# interruptorcontrolado.net
KiCad netlist of a schematic drawn in EAGLE
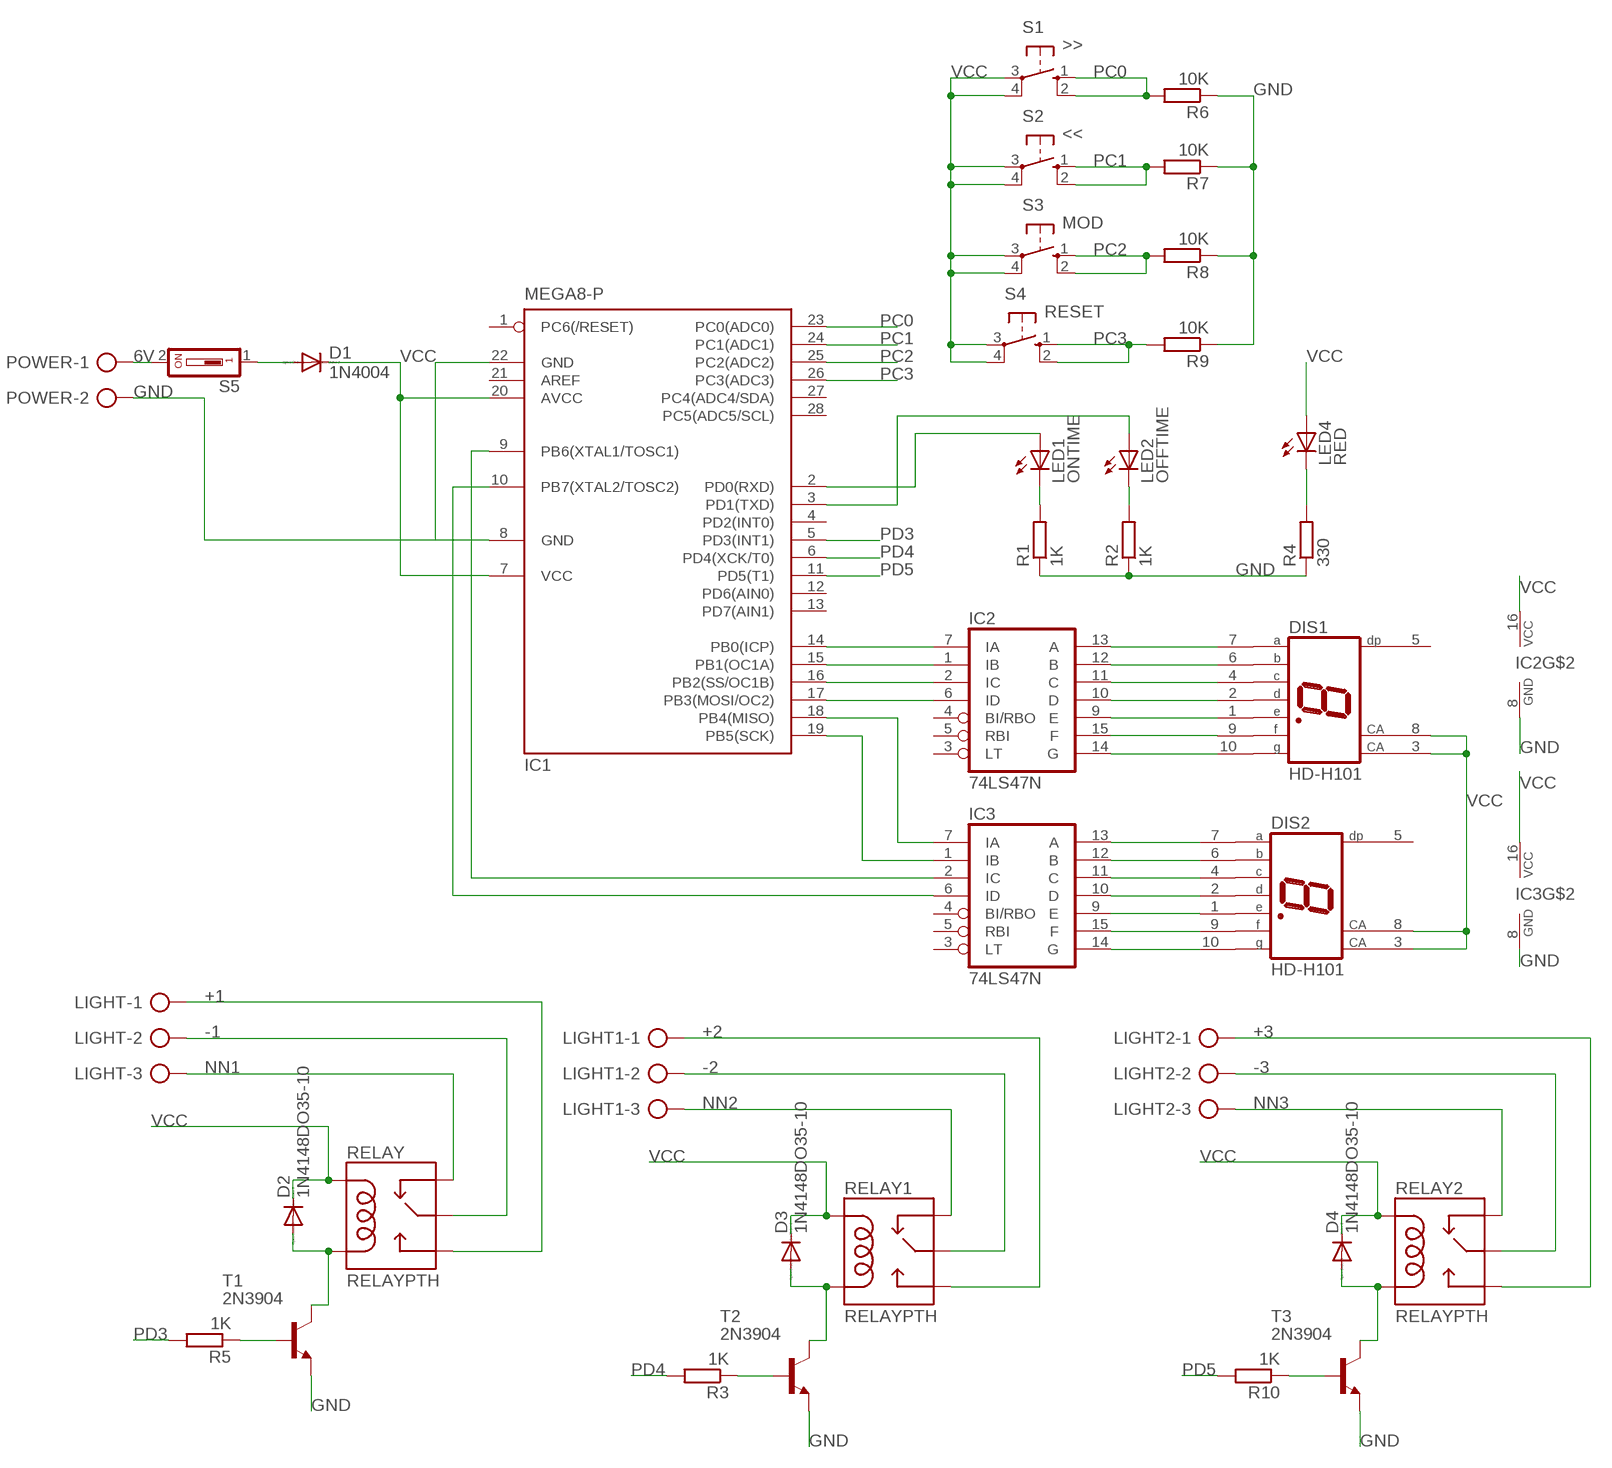
[diagram p0: schematic, sheet 1]

(export (version "E")
  (design (tool "Eeschema 10.0.6"))
  (components
    (comp (ref "D1")
      (value "1N4004")
      (footprint "eagle-import:DO41-10")
      (libsource (lib "eagle-import") (part "1N4004"))
    )
    (comp (ref "D2")
      (value "1N4148DO35-10")
      (footprint "eagle-import:DO35-10")
      (libsource (lib "eagle-import") (part "1N4148DO35-10"))
    )
    (comp (ref "D3")
      (value "1N4148DO35-10")
      (footprint "eagle-import:DO35-10")
      (libsource (lib "eagle-import") (part "1N4148DO35-10"))
    )
    (comp (ref "D4")
      (value "1N4148DO35-10")
      (footprint "eagle-import:DO35-10")
      (libsource (lib "eagle-import") (part "1N4148DO35-10"))
    )
    (comp (ref "DIS1")
      (value "HD-H101")
      (footprint "eagle-import:HDSP-M")
      (libsource (lib "eagle-import") (part "HD-H101"))
    )
    (comp (ref "DIS2")
      (value "HD-H101")
      (footprint "eagle-import:HDSP-M")
      (libsource (lib "eagle-import") (part "HD-H101"))
    )
    (comp (ref "IC1")
      (value "MEGA8-P")
      (footprint "eagle-import:DIL28-3")
      (libsource (lib "eagle-import") (part "MEGA8-P"))
    )
    (comp (ref "IC2")
      (value "74LS47N")
      (footprint "eagle-import:DIL16")
      (libsource (lib "eagle-import") (part "7447NLS"))
    )
    (comp (ref "IC3")
      (value "74LS47N")
      (footprint "eagle-import:DIL16")
      (libsource (lib "eagle-import") (part "7447NLS"))
    )
    (comp (ref "LED1")
      (value "ONTIME")
      (footprint "eagle-import:LED5MM")
      (libsource (lib "eagle-import") (part "LED5MM"))
    )
    (comp (ref "LED2")
      (value "OFFTIME")
      (footprint "eagle-import:LED5MM")
      (libsource (lib "eagle-import") (part "LED5MM"))
    )
    (comp (ref "LED4")
      (value "RED")
      (footprint "eagle-import:LED5MM")
      (libsource (lib "eagle-import") (part "LED5MM"))
    )
    (comp (ref "LIGHT")
      (value "AK500/3")
      (footprint "eagle-import:AK500_3")
      (libsource (lib "eagle-import") (part "AK500/3"))
    )
    (comp (ref "LIGHT1")
      (value "AK500/3")
      (footprint "eagle-import:AK500_3")
      (libsource (lib "eagle-import") (part "AK500/3"))
    )
    (comp (ref "LIGHT2")
      (value "AK500/3")
      (footprint "eagle-import:AK500_3")
      (libsource (lib "eagle-import") (part "AK500/3"))
    )
    (comp (ref "POWER")
      (value "AK500/2")
      (footprint "eagle-import:AK500_2")
      (libsource (lib "eagle-import") (part "AK500/2"))
    )
    (comp (ref "R1")
      (value "1K")
      (footprint "eagle-import:0207_10")
      (libsource (lib "eagle-import") (part "R-EU_0207/10"))
    )
    (comp (ref "R2")
      (value "1K")
      (footprint "eagle-import:0207_10")
      (libsource (lib "eagle-import") (part "R-EU_0207/10"))
    )
    (comp (ref "R3")
      (value "1K")
      (footprint "eagle-import:0207_10")
      (libsource (lib "eagle-import") (part "R-EU_0207/10"))
    )
    (comp (ref "R4")
      (value "330")
      (footprint "eagle-import:0207_10")
      (libsource (lib "eagle-import") (part "R-EU_0207/10"))
    )
    (comp (ref "R5")
      (value "1K")
      (footprint "eagle-import:0207_10")
      (libsource (lib "eagle-import") (part "R-EU_0207/10"))
    )
    (comp (ref "R6")
      (value "10K")
      (footprint "eagle-import:0207_10")
      (libsource (lib "eagle-import") (part "R-EU_0207/10"))
    )
    (comp (ref "R7")
      (value "10K")
      (footprint "eagle-import:0207_10")
      (libsource (lib "eagle-import") (part "R-EU_0207/10"))
    )
    (comp (ref "R8")
      (value "10K")
      (footprint "eagle-import:0207_10")
      (libsource (lib "eagle-import") (part "R-EU_0207/10"))
    )
    (comp (ref "R9")
      (value "10K")
      (footprint "eagle-import:0207_10")
      (libsource (lib "eagle-import") (part "R-EU_0207/10"))
    )
    (comp (ref "R10")
      (value "1K")
      (footprint "eagle-import:0207_10")
      (libsource (lib "eagle-import") (part "R-EU_0207/10"))
    )
    (comp (ref "RELAY")
      (value "RELAYPTH")
      (footprint "eagle-import:SRD-05VDC-SL-C")
      (libsource (lib "eagle-import") (part "RELAYPTH"))
    )
    (comp (ref "RELAY1")
      (value "RELAYPTH")
      (footprint "eagle-import:SRD-05VDC-SL-C")
      (libsource (lib "eagle-import") (part "RELAYPTH"))
    )
    (comp (ref "RELAY2")
      (value "RELAYPTH")
      (footprint "eagle-import:SRD-05VDC-SL-C")
      (libsource (lib "eagle-import") (part "RELAYPTH"))
    )
    (comp (ref "S1")
      (value ">>")
      (footprint "eagle-import:B3F-10XX")
      (fields (field (name "MPN") "B3F-1000"))
      (libsource (lib "eagle-import") (part "10-XX"))
    )
    (comp (ref "S2")
      (value "<<")
      (footprint "eagle-import:B3F-10XX")
      (fields (field (name "MPN") "B3F-1000"))
      (libsource (lib "eagle-import") (part "10-XX"))
    )
    (comp (ref "S3")
      (value "MOD")
      (footprint "eagle-import:B3F-10XX")
      (fields (field (name "MPN") "B3F-1000"))
      (libsource (lib "eagle-import") (part "10-XX"))
    )
    (comp (ref "S4")
      (value "RESET")
      (footprint "eagle-import:B3F-10XX")
      (fields (field (name "MPN") "B3F-1000"))
      (libsource (lib "eagle-import") (part "10-XX"))
    )
    (comp (ref "S5")
      (value "SD4-01")
      (footprint "eagle-import:SD4-01")
      (libsource (lib "eagle-import") (part "SD4-01"))
    )
    (comp (ref "T1")
      (value "2N3904")
      (footprint "eagle-import:TO92")
      (libsource (lib "eagle-import") (part "2N3904"))
    )
    (comp (ref "T2")
      (value "2N3904")
      (footprint "eagle-import:TO92")
      (libsource (lib "eagle-import") (part "2N3904"))
    )
    (comp (ref "T3")
      (value "2N3904")
      (footprint "eagle-import:TO92")
      (libsource (lib "eagle-import") (part "2N3904"))
    )
  )
  (nets
    (net (code "1") (name "/+1") (class "Default")
      (node (ref "LIGHT") (pin "1") (pinfunction "KL_1") (pintype "passive"))
      (node (ref "RELAY") (pin "SWOPEN") (pinfunction "SWOPEN_SWOPEN") (pintype "bidirectional"))
    )
    (net (code "2") (name "/+2") (class "Default")
      (node (ref "LIGHT1") (pin "1") (pinfunction "KL_1") (pintype "passive"))
      (node (ref "RELAY1") (pin "SWOPEN") (pinfunction "SWOPEN_SWOPEN") (pintype "bidirectional"))
    )
    (net (code "3") (name "/+3") (class "Default")
      (node (ref "LIGHT2") (pin "1") (pinfunction "KL_1") (pintype "passive"))
      (node (ref "RELAY2") (pin "SWOPEN") (pinfunction "SWOPEN_SWOPEN") (pintype "bidirectional"))
    )
    (net (code "4") (name "/-1") (class "Default")
      (node (ref "LIGHT") (pin "2") (pinfunction "KL_2") (pintype "passive"))
      (node (ref "RELAY") (pin "SWCOMMON") (pinfunction "SWCOMMON_SWCOMMON") (pintype "bidirectional"))
    )
    (net (code "5") (name "/-2") (class "Default")
      (node (ref "LIGHT1") (pin "2") (pinfunction "KL_2") (pintype "passive"))
      (node (ref "RELAY1") (pin "SWCOMMON") (pinfunction "SWCOMMON_SWCOMMON") (pintype "bidirectional"))
    )
    (net (code "6") (name "/-3") (class "Default")
      (node (ref "LIGHT2") (pin "2") (pinfunction "KL_2") (pintype "passive"))
      (node (ref "RELAY2") (pin "SWCOMMON") (pinfunction "SWCOMMON_SWCOMMON") (pintype "bidirectional"))
    )
    (net (code "7") (name "/6V") (class "Default")
      (node (ref "POWER") (pin "1") (pinfunction "KL_1") (pintype "passive"))
      (node (ref "S5") (pin "2") (pinfunction "2_2") (pintype "passive"))
    )
    (net (code "8") (name "/GND") (class "Default")
      (node (ref "IC1") (pin "22") (pinfunction "GND_22") (pintype "power_in"))
      (node (ref "IC1") (pin "8") (pinfunction "GND_8") (pintype "power_in"))
      (node (ref "IC2") (pin "8") (pinfunction "GND_8") (pintype "power_in"))
      (node (ref "IC3") (pin "8") (pinfunction "GND_8") (pintype "power_in"))
      (node (ref "POWER") (pin "2") (pinfunction "KL_2") (pintype "passive"))
      (node (ref "R1") (pin "1") (pinfunction "1_1") (pintype "passive"))
      (node (ref "R2") (pin "1") (pinfunction "1_1") (pintype "passive"))
      (node (ref "R4") (pin "1") (pinfunction "1_1") (pintype "passive"))
      (node (ref "R6") (pin "1") (pinfunction "1_1") (pintype "passive"))
      (node (ref "R7") (pin "1") (pinfunction "1_1") (pintype "passive"))
      (node (ref "R8") (pin "1") (pinfunction "1_1") (pintype "passive"))
      (node (ref "R9") (pin "1") (pinfunction "1_1") (pintype "passive"))
      (node (ref "T1") (pin "3") (pinfunction "E_3") (pintype "passive"))
      (node (ref "T2") (pin "3") (pinfunction "E_3") (pintype "passive"))
      (node (ref "T3") (pin "3") (pinfunction "E_3") (pintype "passive"))
    )
    (net (code "9") (name "/NN1") (class "Default")
      (node (ref "LIGHT") (pin "3") (pinfunction "KL_3") (pintype "passive"))
      (node (ref "RELAY") (pin "SWCLOSED") (pinfunction "SWCLOSE_SWCLOSED") (pintype "bidirectional"))
    )
    (net (code "10") (name "/NN2") (class "Default")
      (node (ref "LIGHT1") (pin "3") (pinfunction "KL_3") (pintype "passive"))
      (node (ref "RELAY1") (pin "SWCLOSED") (pinfunction "SWCLOSE_SWCLOSED") (pintype "bidirectional"))
    )
    (net (code "11") (name "/NN3") (class "Default")
      (node (ref "LIGHT2") (pin "3") (pinfunction "KL_3") (pintype "passive"))
      (node (ref "RELAY2") (pin "SWCLOSED") (pinfunction "SWCLOSE_SWCLOSED") (pintype "bidirectional"))
    )
    (net (code "12") (name "/PC0") (class "Default")
      (node (ref "IC1") (pin "23") (pinfunction "PC0(ADC0)_23") (pintype "bidirectional"))
      (node (ref "R6") (pin "2") (pinfunction "2_2") (pintype "passive"))
      (node (ref "S1") (pin "1") (pinfunction "S_1") (pintype "passive"))
      (node (ref "S1") (pin "2") (pinfunction "S1_2") (pintype "passive"))
    )
    (net (code "13") (name "/PC1") (class "Default")
      (node (ref "IC1") (pin "24") (pinfunction "PC1(ADC1)_24") (pintype "bidirectional"))
      (node (ref "R7") (pin "2") (pinfunction "2_2") (pintype "passive"))
      (node (ref "S2") (pin "1") (pinfunction "S_1") (pintype "passive"))
      (node (ref "S2") (pin "2") (pinfunction "S1_2") (pintype "passive"))
    )
    (net (code "14") (name "/PC2") (class "Default")
      (node (ref "IC1") (pin "25") (pinfunction "PC2(ADC2)_25") (pintype "bidirectional"))
      (node (ref "R8") (pin "2") (pinfunction "2_2") (pintype "passive"))
      (node (ref "S3") (pin "1") (pinfunction "S_1") (pintype "passive"))
      (node (ref "S3") (pin "2") (pinfunction "S1_2") (pintype "passive"))
    )
    (net (code "15") (name "/PC3") (class "Default")
      (node (ref "IC1") (pin "26") (pinfunction "PC3(ADC3)_26") (pintype "bidirectional"))
      (node (ref "R9") (pin "2") (pinfunction "2_2") (pintype "passive"))
      (node (ref "S4") (pin "1") (pinfunction "S_1") (pintype "passive"))
      (node (ref "S4") (pin "2") (pinfunction "S1_2") (pintype "passive"))
    )
    (net (code "16") (name "/PD3") (class "Default")
      (node (ref "IC1") (pin "5") (pinfunction "PD3(INT1)_5") (pintype "bidirectional"))
      (node (ref "R5") (pin "2") (pinfunction "2_2") (pintype "passive"))
    )
    (net (code "17") (name "/PD4") (class "Default")
      (node (ref "IC1") (pin "6") (pinfunction "PD4(XCK/T0)_6") (pintype "bidirectional"))
      (node (ref "R3") (pin "2") (pinfunction "2_2") (pintype "passive"))
    )
    (net (code "18") (name "/PD5") (class "Default")
      (node (ref "IC1") (pin "11") (pinfunction "PD5(T1)_11") (pintype "bidirectional"))
      (node (ref "R10") (pin "2") (pinfunction "2_2") (pintype "passive"))
    )
    (net (code "19") (name "/VCC") (class "Default")
      (node (ref "D1") (pin "C") (pinfunction "C_C") (pintype "passive"))
      (node (ref "D2") (pin "C") (pinfunction "C_C") (pintype "passive"))
      (node (ref "D3") (pin "C") (pinfunction "C_C") (pintype "passive"))
      (node (ref "D4") (pin "C") (pinfunction "C_C") (pintype "passive"))
      (node (ref "DIS1") (pin "3") (pinfunction "CA_3") (pintype "passive"))
      (node (ref "DIS1") (pin "8") (pinfunction "CA_8") (pintype "passive"))
      (node (ref "DIS2") (pin "3") (pinfunction "CA_3") (pintype "passive"))
      (node (ref "DIS2") (pin "8") (pinfunction "CA_8") (pintype "passive"))
      (node (ref "IC1") (pin "20") (pinfunction "AVCC_20") (pintype "power_in"))
      (node (ref "IC1") (pin "7") (pinfunction "VCC_7") (pintype "power_in"))
      (node (ref "IC2") (pin "16") (pinfunction "VCC_16") (pintype "power_in"))
      (node (ref "IC3") (pin "16") (pinfunction "VCC_16") (pintype "power_in"))
      (node (ref "LED4") (pin "A") (pinfunction "A_A") (pintype "passive"))
      (node (ref "RELAY") (pin "COIL1") (pinfunction "COIL1_COIL1") (pintype "bidirectional"))
      (node (ref "RELAY1") (pin "COIL1") (pinfunction "COIL1_COIL1") (pintype "bidirectional"))
      (node (ref "RELAY2") (pin "COIL1") (pinfunction "COIL1_COIL1") (pintype "bidirectional"))
      (node (ref "S1") (pin "3") (pinfunction "P_3") (pintype "passive"))
      (node (ref "S1") (pin "4") (pinfunction "P1_4") (pintype "passive"))
      (node (ref "S2") (pin "3") (pinfunction "P_3") (pintype "passive"))
      (node (ref "S2") (pin "4") (pinfunction "P1_4") (pintype "passive"))
      (node (ref "S3") (pin "3") (pinfunction "P_3") (pintype "passive"))
      (node (ref "S3") (pin "4") (pinfunction "P1_4") (pintype "passive"))
      (node (ref "S4") (pin "3") (pinfunction "P_3") (pintype "passive"))
      (node (ref "S4") (pin "4") (pinfunction "P1_4") (pintype "passive"))
    )
    (net (code "20") (name "Net-(D1-PadA)") (class "Default")
      (node (ref "D1") (pin "A") (pinfunction "A_A") (pintype "passive"))
      (node (ref "S5") (pin "1") (pinfunction "1_1") (pintype "passive"))
    )
    (net (code "21") (name "Net-(DIS1-A)") (class "Default")
      (node (ref "DIS1") (pin "7") (pinfunction "A_7") (pintype "passive"))
      (node (ref "IC2") (pin "13") (pinfunction "A_13") (pintype "output"))
    )
    (net (code "22") (name "Net-(DIS1-B)") (class "Default")
      (node (ref "DIS1") (pin "6") (pinfunction "B_6") (pintype "passive"))
      (node (ref "IC2") (pin "12") (pinfunction "B_12") (pintype "output"))
    )
    (net (code "23") (name "Net-(DIS1-C)") (class "Default")
      (node (ref "DIS1") (pin "4") (pinfunction "C_4") (pintype "passive"))
      (node (ref "IC2") (pin "11") (pinfunction "C_11") (pintype "output"))
    )
    (net (code "24") (name "Net-(DIS1-D)") (class "Default")
      (node (ref "DIS1") (pin "2") (pinfunction "D_2") (pintype "passive"))
      (node (ref "IC2") (pin "10") (pinfunction "D_10") (pintype "output"))
    )
    (net (code "25") (name "Net-(DIS1-E)") (class "Default")
      (node (ref "DIS1") (pin "1") (pinfunction "E_1") (pintype "passive"))
      (node (ref "IC2") (pin "9") (pinfunction "E_9") (pintype "output"))
    )
    (net (code "26") (name "Net-(DIS1-F)") (class "Default")
      (node (ref "DIS1") (pin "9") (pinfunction "F_9") (pintype "passive"))
      (node (ref "IC2") (pin "15") (pinfunction "F_15") (pintype "output"))
    )
    (net (code "27") (name "Net-(DIS1-G)") (class "Default")
      (node (ref "DIS1") (pin "10") (pinfunction "G_10") (pintype "passive"))
      (node (ref "IC2") (pin "14") (pinfunction "G_14") (pintype "output"))
    )
    (net (code "28") (name "Net-(DIS2-A)") (class "Default")
      (node (ref "DIS2") (pin "7") (pinfunction "A_7") (pintype "passive"))
      (node (ref "IC3") (pin "13") (pinfunction "A_13") (pintype "output"))
    )
    (net (code "29") (name "Net-(DIS2-B)") (class "Default")
      (node (ref "DIS2") (pin "6") (pinfunction "B_6") (pintype "passive"))
      (node (ref "IC3") (pin "12") (pinfunction "B_12") (pintype "output"))
    )
    (net (code "30") (name "Net-(DIS2-C)") (class "Default")
      (node (ref "DIS2") (pin "4") (pinfunction "C_4") (pintype "passive"))
      (node (ref "IC3") (pin "11") (pinfunction "C_11") (pintype "output"))
    )
    (net (code "31") (name "Net-(DIS2-D)") (class "Default")
      (node (ref "DIS2") (pin "2") (pinfunction "D_2") (pintype "passive"))
      (node (ref "IC3") (pin "10") (pinfunction "D_10") (pintype "output"))
    )
    (net (code "32") (name "Net-(DIS2-E)") (class "Default")
      (node (ref "DIS2") (pin "1") (pinfunction "E_1") (pintype "passive"))
      (node (ref "IC3") (pin "9") (pinfunction "E_9") (pintype "output"))
    )
    (net (code "33") (name "Net-(DIS2-F)") (class "Default")
      (node (ref "DIS2") (pin "9") (pinfunction "F_9") (pintype "passive"))
      (node (ref "IC3") (pin "15") (pinfunction "F_15") (pintype "output"))
    )
    (net (code "34") (name "Net-(DIS2-G)") (class "Default")
      (node (ref "DIS2") (pin "10") (pinfunction "G_10") (pintype "passive"))
      (node (ref "IC3") (pin "14") (pinfunction "G_14") (pintype "output"))
    )
    (net (code "35") (name "Net-(IC1-PB0(ICP))") (class "Default")
      (node (ref "IC1") (pin "14") (pinfunction "PB0(ICP)_14") (pintype "bidirectional"))
      (node (ref "IC2") (pin "7") (pinfunction "IA_7") (pintype "input"))
    )
    (net (code "36") (name "Net-(IC1-PB1(OC1A))") (class "Default")
      (node (ref "IC1") (pin "15") (pinfunction "PB1(OC1A)_15") (pintype "bidirectional"))
      (node (ref "IC2") (pin "1") (pinfunction "IB_1") (pintype "input"))
    )
    (net (code "37") (name "Net-(IC1-PB2(SS{slash}OC1B))") (class "Default")
      (node (ref "IC1") (pin "16") (pinfunction "PB2(SS/OC1B)_16") (pintype "bidirectional"))
      (node (ref "IC2") (pin "2") (pinfunction "IC_2") (pintype "input"))
    )
    (net (code "38") (name "Net-(IC1-PB3(MOSI{slash}OC2))") (class "Default")
      (node (ref "IC1") (pin "17") (pinfunction "PB3(MOSI/OC2)_17") (pintype "bidirectional"))
      (node (ref "IC2") (pin "6") (pinfunction "ID_6") (pintype "input"))
    )
    (net (code "39") (name "Net-(IC1-PB4(MISO))") (class "Default")
      (node (ref "IC1") (pin "18") (pinfunction "PB4(MISO)_18") (pintype "bidirectional"))
      (node (ref "IC3") (pin "7") (pinfunction "IA_7") (pintype "input"))
    )
    (net (code "40") (name "Net-(IC1-PB5(SCK))") (class "Default")
      (node (ref "IC1") (pin "19") (pinfunction "PB5(SCK)_19") (pintype "bidirectional"))
      (node (ref "IC3") (pin "1") (pinfunction "IB_1") (pintype "input"))
    )
    (net (code "41") (name "Net-(IC1-PB6(XTAL1{slash}TOSC1))") (class "Default")
      (node (ref "IC1") (pin "9") (pinfunction "PB6(XTAL1/TOSC1)_9") (pintype "bidirectional"))
      (node (ref "IC3") (pin "2") (pinfunction "IC_2") (pintype "input"))
    )
    (net (code "42") (name "Net-(IC1-PB7(XTAL2{slash}TOSC2))") (class "Default")
      (node (ref "IC1") (pin "10") (pinfunction "PB7(XTAL2/TOSC2)_10") (pintype "bidirectional"))
      (node (ref "IC3") (pin "6") (pinfunction "ID_6") (pintype "input"))
    )
    (net (code "43") (name "Net-(IC1-PD0(RXD))") (class "Default")
      (node (ref "IC1") (pin "2") (pinfunction "PD0(RXD)_2") (pintype "bidirectional"))
      (node (ref "LED1") (pin "A") (pinfunction "A_A") (pintype "passive"))
    )
    (net (code "44") (name "Net-(IC1-PD1(TXD))") (class "Default")
      (node (ref "IC1") (pin "3") (pinfunction "PD1(TXD)_3") (pintype "bidirectional"))
      (node (ref "LED2") (pin "A") (pinfunction "A_A") (pintype "passive"))
    )
    (net (code "45") (name "Net-(LED1-C)") (class "Default")
      (node (ref "LED1") (pin "K") (pinfunction "C_K") (pintype "passive"))
      (node (ref "R1") (pin "2") (pinfunction "2_2") (pintype "passive"))
    )
    (net (code "46") (name "Net-(LED2-C)") (class "Default")
      (node (ref "LED2") (pin "K") (pinfunction "C_K") (pintype "passive"))
      (node (ref "R2") (pin "2") (pinfunction "2_2") (pintype "passive"))
    )
    (net (code "47") (name "Net-(LED4-C)") (class "Default")
      (node (ref "LED4") (pin "K") (pinfunction "C_K") (pintype "passive"))
      (node (ref "R4") (pin "2") (pinfunction "2_2") (pintype "passive"))
    )
    (net (code "48") (name "Net-(T1-B)") (class "Default")
      (node (ref "R5") (pin "1") (pinfunction "1_1") (pintype "passive"))
      (node (ref "T1") (pin "2") (pinfunction "B_2") (pintype "passive"))
    )
    (net (code "49") (name "Net-(T1-C)") (class "Default")
      (node (ref "D2") (pin "A") (pinfunction "A_A") (pintype "passive"))
      (node (ref "RELAY") (pin "COIL0") (pinfunction "COIL0_COIL0") (pintype "bidirectional"))
      (node (ref "T1") (pin "1") (pinfunction "C_1") (pintype "passive"))
    )
    (net (code "50") (name "Net-(T2-B)") (class "Default")
      (node (ref "R3") (pin "1") (pinfunction "1_1") (pintype "passive"))
      (node (ref "T2") (pin "2") (pinfunction "B_2") (pintype "passive"))
    )
    (net (code "51") (name "Net-(T2-C)") (class "Default")
      (node (ref "D3") (pin "A") (pinfunction "A_A") (pintype "passive"))
      (node (ref "RELAY1") (pin "COIL0") (pinfunction "COIL0_COIL0") (pintype "bidirectional"))
      (node (ref "T2") (pin "1") (pinfunction "C_1") (pintype "passive"))
    )
    (net (code "52") (name "Net-(T3-B)") (class "Default")
      (node (ref "R10") (pin "1") (pinfunction "1_1") (pintype "passive"))
      (node (ref "T3") (pin "2") (pinfunction "B_2") (pintype "passive"))
    )
    (net (code "53") (name "Net-(T3-C)") (class "Default")
      (node (ref "D4") (pin "A") (pinfunction "A_A") (pintype "passive"))
      (node (ref "RELAY2") (pin "COIL0") (pinfunction "COIL0_COIL0") (pintype "bidirectional"))
      (node (ref "T3") (pin "1") (pinfunction "C_1") (pintype "passive"))
    )
    (net (code "54") (name "unconnected-(DIS1-DP-Pad5)") (class "Default")
      (node (ref "DIS1") (pin "5") (pinfunction "DP_5") (pintype "passive"))
    )
    (net (code "55") (name "unconnected-(DIS2-DP-Pad5)") (class "Default")
      (node (ref "DIS2") (pin "5") (pinfunction "DP_5") (pintype "passive"))
    )
    (net (code "56") (name "unconnected-(IC1-AREF-Pad21)") (class "Default")
      (node (ref "IC1") (pin "21") (pinfunction "AREF_21") (pintype "passive"))
    )
    (net (code "57") (name "unconnected-(IC1-PC4(ADC4{slash}SDA)-Pad27)") (class "Default")
      (node (ref "IC1") (pin "27") (pinfunction "PC4(ADC4/SDA)_27") (pintype "bidirectional"))
    )
    (net (code "58") (name "unconnected-(IC1-PC5(ADC5{slash}SCL)-Pad28)") (class "Default")
      (node (ref "IC1") (pin "28") (pinfunction "PC5(ADC5/SCL)_28") (pintype "bidirectional"))
    )
    (net (code "59") (name "unconnected-(IC1-PC6({slash}RESET)-Pad1)") (class "Default")
      (node (ref "IC1") (pin "1") (pinfunction "PC6(/RESET)_1") (pintype "bidirectional"))
    )
    (net (code "60") (name "unconnected-(IC1-PD2(INT0)-Pad4)") (class "Default")
      (node (ref "IC1") (pin "4") (pinfunction "PD2(INT0)_4") (pintype "bidirectional"))
    )
    (net (code "61") (name "unconnected-(IC1-PD6(AIN0)-Pad12)") (class "Default")
      (node (ref "IC1") (pin "12") (pinfunction "PD6(AIN0)_12") (pintype "bidirectional"))
    )
    (net (code "62") (name "unconnected-(IC1-PD7(AIN1)-Pad13)") (class "Default")
      (node (ref "IC1") (pin "13") (pinfunction "PD7(AIN1)_13") (pintype "bidirectional"))
    )
    (net (code "63") (name "unconnected-(IC2A-BI{slash}RBO-Pad4)") (class "Default")
      (node (ref "IC2") (pin "4") (pinfunction "BI/RBO_4") (pintype "input"))
    )
    (net (code "64") (name "unconnected-(IC2A-LT-Pad3)") (class "Default")
      (node (ref "IC2") (pin "3") (pinfunction "LT_3") (pintype "input"))
    )
    (net (code "65") (name "unconnected-(IC2A-RBI-Pad5)") (class "Default")
      (node (ref "IC2") (pin "5") (pinfunction "RBI_5") (pintype "input"))
    )
    (net (code "66") (name "unconnected-(IC3A-BI{slash}RBO-Pad4)") (class "Default")
      (node (ref "IC3") (pin "4") (pinfunction "BI/RBO_4") (pintype "input"))
    )
    (net (code "67") (name "unconnected-(IC3A-LT-Pad3)") (class "Default")
      (node (ref "IC3") (pin "3") (pinfunction "LT_3") (pintype "input"))
    )
    (net (code "68") (name "unconnected-(IC3A-RBI-Pad5)") (class "Default")
      (node (ref "IC3") (pin "5") (pinfunction "RBI_5") (pintype "input"))
    )
  )
)
